# cc2520_cc2592.net
KiCad netlist of a schematic drawn in Altium Designer
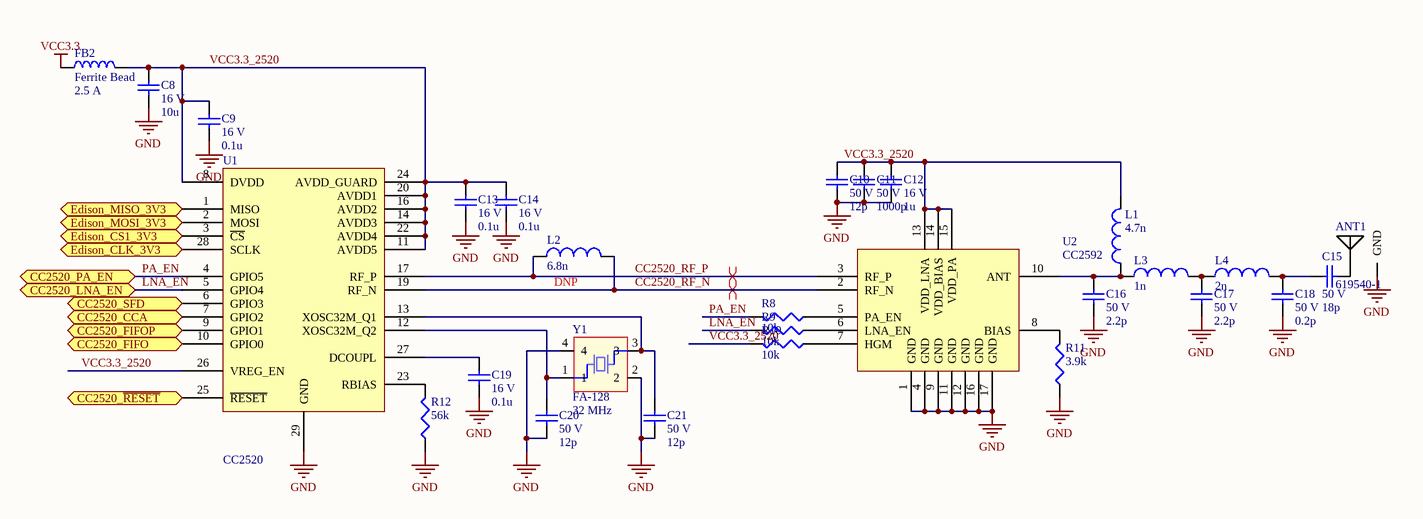
[diagram p0: cc2520_cc2592.SchDoc]

(export (version "E")
  (design (tool "Eeschema 10.0.6"))
  (components
    (comp (ref "ANT1")
      (value "619540-1")
      (footprint "619540-1")
      (description "CONN SMA JACK")
      (libsource (lib "RF") (part "619540-1"))
    )
    (comp (ref "C8")
      (value "10u")
      (footprint "0603")
      (description "10µF ±20% 16V Ceramic Capacitor X6S 0603")
      (fields
        (field (name "TOLERANCE") "20%")
        (field (name "VOLTAGE RATED") "16 V")
        (field (name "MANUFACTURER PART NUMBER") "GRM188C81C106MA73D")
      )
      (libsource (lib "capacitors") (part "GRM188C81C106MA73D"))
    )
    (comp (ref "C9")
      (value "0.1u")
      (footprint "0402")
      (description "0.10µF ±10% 16V Ceramic Capacitor X7R 0402")
      (fields
        (field (name "TOLERANCE") "10%")
        (field (name "VOLTAGE RATED") "16 V")
        (field (name "MANUFACTURER PART NUMBER") "GRM155R71C104KA88D")
      )
      (libsource (lib "capacitors") (part "GRM155R71C104KA88D"))
    )
    (comp (ref "C10")
      (value "12p")
      (footprint "0402")
      (description "12pF ±2% 50V Ceramic Capacitor C0G, NP0 0402")
      (fields
        (field (name "VOLTAGE RATED") "50 V")
        (field (name "TOLERANCE") "2%")
        (field (name "MANUFACTURER PART NUMBER") "500R07S120GV4T")
      )
      (libsource (lib "capacitors") (part "500R07S120GV4T"))
    )
    (comp (ref "C11")
      (value "1000p")
      (footprint "0402")
      (description "1000pF ±5% 50V Ceramic Capacitor C0G, NP0 0402")
      (fields
        (field (name "VOLTAGE RATED") "50 V")
        (field (name "TOLERANCE") "5%")
        (field (name "MANUFACTURER PART NUMBER") "C1005C0G1H102J050BA")
      )
      (libsource (lib "capacitors") (part "C1005C0G1H102J050BA"))
    )
    (comp (ref "C12")
      (value "1u")
      (footprint "0402")
      (description "1µF ±10% 16V Ceramic Capacitor X6S 0402")
      (fields
        (field (name "VOLTAGE RATED") "16 V")
        (field (name "TOLERANCE") "10%")
        (field (name "MANUFACTURER PART NUMBER") "C1005X6S1C105K050BC")
      )
      (libsource (lib "capacitors") (part "C1005X6S1C105K050BC"))
    )
    (comp (ref "C13")
      (value "0.1u")
      (footprint "0402")
      (description "0.10µF ±10% 16V Ceramic Capacitor X7R 0402")
      (fields
        (field (name "TOLERANCE") "10%")
        (field (name "VOLTAGE RATED") "16 V")
        (field (name "MANUFACTURER PART NUMBER") "GRM155R71C104KA88D")
      )
      (libsource (lib "capacitors") (part "GRM155R71C104KA88D"))
    )
    (comp (ref "C14")
      (value "0.1u")
      (footprint "0402")
      (description "0.10µF ±10% 16V Ceramic Capacitor X7R 0402")
      (fields
        (field (name "TOLERANCE") "10%")
        (field (name "VOLTAGE RATED") "16 V")
        (field (name "MANUFACTURER PART NUMBER") "GRM155R71C104KA88D")
      )
      (libsource (lib "capacitors") (part "GRM155R71C104KA88D"))
    )
    (comp (ref "C15")
      (value "18p")
      (footprint "0402")
      (description "18pF ±2% 50V Ceramic Capacitor C0G, NP0 0402")
      (fields
        (field (name "TOLERANCE") "2%")
        (field (name "VOLTAGE RATED") "50 V")
        (field (name "MANUFACTURER PART NUMBER") "500R07S180GV4T")
      )
      (libsource (lib "capacitors") (part "500R07S180GV4T"))
    )
    (comp (ref "C16")
      (value "2.2p")
      (footprint "0402")
      (description "2.2pF ±0.1pF 50V Ceramic Capacitor C0G, NP0")
      (fields
        (field (name "TOLERANCE") "0.1p")
        (field (name "VOLTAGE RATED") "50 V")
        (field (name "MANUFACTURER PART NUMBER") "500R07S2R2BV4T")
      )
      (libsource (lib "capacitors") (part "500R07S2R2BV4T"))
    )
    (comp (ref "C17")
      (value "2.2p")
      (footprint "0402")
      (description "2.2pF ±0.1pF 50V Ceramic Capacitor C0G, NP0")
      (fields
        (field (name "TOLERANCE") "0.1p")
        (field (name "VOLTAGE RATED") "50 V")
        (field (name "MANUFACTURER PART NUMBER") "500R07S2R2BV4T")
      )
      (libsource (lib "capacitors") (part "500R07S2R2BV4T"))
    )
    (comp (ref "C18")
      (value "0.2p")
      (footprint "0402")
      (description "0.20pF ±0.05pF 50V Ceramic Capacitor C0G, NP0 0402")
      (fields
        (field (name "TOLERANCE") "0.05p")
        (field (name "VOLTAGE RATED") "50 V")
        (field (name "MANUFACTURER PART NUMBER") "500R07S0R2AV4T")
      )
      (libsource (lib "capacitors") (part "500R07S0R2AV4T"))
    )
    (comp (ref "C19")
      (value "0.1u")
      (footprint "0402")
      (description "0.10µF ±10% 16V Ceramic Capacitor X7R 0402")
      (fields
        (field (name "TOLERANCE") "10%")
        (field (name "VOLTAGE RATED") "16 V")
        (field (name "MANUFACTURER PART NUMBER") "GRM155R71C104KA88D")
      )
      (libsource (lib "capacitors") (part "GRM155R71C104KA88D"))
    )
    (comp (ref "C20")
      (value "12p")
      (footprint "0402")
      (description "12pF ±2% 50V Ceramic Capacitor C0G, NP0 0402")
      (fields
        (field (name "VOLTAGE RATED") "50 V")
        (field (name "TOLERANCE") "2%")
        (field (name "MANUFACTURER PART NUMBER") "500R07S120GV4T")
      )
      (libsource (lib "capacitors") (part "500R07S120GV4T"))
    )
    (comp (ref "C21")
      (value "12p")
      (footprint "0402")
      (description "12pF ±2% 50V Ceramic Capacitor C0G, NP0 0402")
      (fields
        (field (name "VOLTAGE RATED") "50 V")
        (field (name "TOLERANCE") "2%")
        (field (name "MANUFACTURER PART NUMBER") "500R07S120GV4T")
      )
      (libsource (lib "capacitors") (part "500R07S120GV4T"))
    )
    (comp (ref "FB2")
      (value "Ferrite Bead")
      (footprint "0603")
      (description "FERRITE BEAD 220 OHM 0603")
      (fields
        (field (name "MANUFACTURER PART NUMBER") "BLM18SG221TN1D")
        (field (name "MANUFACTURER") "Murata")
        (field (name "CURRENT RATING (MAX)") "2.5 A")
      )
      (libsource (lib "ferrite_beads") (part "BLM18SG221TN1D"))
    )
    (comp (ref "L1")
      (value "4.7n")
      (footprint "0402")
      (description "4.7nH Unshielded Multilayer Inductor 300mA 180 mOhm Max 0402 (1005 Metric)")
      (fields (field (name "TOLERANCE") "0.3n") (field (name "MANUFACTURER PART NUMBER") "LQG15HS4N7S02D"))
      (libsource (lib "inductors") (part "LQG15HS4N7S02D"))
    )
    (comp (ref "L2")
      (value "6.8n")
      (footprint "0402")
      (description "6.8nH Unshielded Multilayer Inductor 250mA 320 mOhm Max 0402 (1005 Metric)")
      (fields
        (field (name "TOLERANCE") "5%")
        (field (name "MANUFACTURER PART NUMBER") "L-07C6N8JV6T")
        (field (name "NOTE") "DNP")
      )
      (libsource (lib "inductors") (part "L-07C6N8JV6T"))
    )
    (comp (ref "L3")
      (value "1n")
      (footprint "0402")
      (description "1nH Unshielded Multilayer Inductor 300mA 100 mOhm Max 0402 (1005 Metric)")
      (fields (field (name "TOLERANCE") "0.3n") (field (name "MANUFACTURER PART NUMBER") "LQG15HN1N0S02D"))
      (libsource (lib "inductors") (part "LQG15HN1N0S02D"))
    )
    (comp (ref "L4")
      (value "2n")
      (footprint "0402")
      (description "2nH Unshielded Multilayer Inductor 300mA 120 mOhm Max 0402 (1005 Metric)")
      (fields (field (name "TOLERANCE") "0.3n") (field (name "MANUFACTURER PART NUMBER") "LQG15HN2N0S02D"))
      (libsource (lib "inductors") (part "LQG15HN2N0S02D"))
    )
    (comp (ref "R8")
      (value "10k")
      (footprint "0402")
      (description "RES SMD 10K OHM 1% 1/16W 0402")
      (fields (field (name "TOLERANCE") "1%") (field (name "POWER") "1/16 W"))
      (libsource (lib "resistors") (part "CRCW040210K0FKED"))
    )
    (comp (ref "R9")
      (value "10k")
      (footprint "0402")
      (description "RES SMD 10K OHM 1% 1/16W 0402")
      (fields (field (name "TOLERANCE") "1%") (field (name "POWER") "1/16 W"))
      (libsource (lib "resistors") (part "CRCW040210K0FKED"))
    )
    (comp (ref "R10")
      (value "10k")
      (footprint "0402")
      (description "RES SMD 10K OHM 1% 1/16W 0402")
      (fields (field (name "TOLERANCE") "1%") (field (name "POWER") "1/16 W"))
      (libsource (lib "resistors") (part "CRCW040210K0FKED"))
    )
    (comp (ref "R11")
      (value "3.9k")
      (footprint "0402")
      (description "RES SMD 3.9K OHM 1% 1/16W 0402")
      (fields (field (name "TOLERANCE") "1%") (field (name "POWER") "1/16 W"))
      (libsource (lib "resistors") (part "RC0402FR-073K9L"))
    )
    (comp (ref "R12")
      (value "56k")
      (footprint "0402")
      (description "RES SMD 56K OHM 1% 1/16W 0402")
      (fields (field (name "POWER") "1/16 W") (field (name "TOLERANCE") "1%"))
      (libsource (lib "resistors") (part "CRCW040256K0FKED"))
    )
    (comp (ref "U1")
      (value "CC2520")
      (footprint "QFN-28")
      (description "2.4 GHZ IEEE 802.15.4/ZIGBEE® RF TRANSCEIVER")
      (libsource (lib "RF") (part "CC2520"))
    )
    (comp (ref "U2")
      (value "CC2592")
      (footprint "RF:QFN-16")
      (description "2.4-GHz Range Extender")
      (libsource (lib "RF") (part "CC2592"))
    )
    (comp (ref "Y1")
      (value "FA-128")
      (footprint "FA-128")
      (description "MHz Range Crystal Unit")
      (fields (field (name "FREQUENCY") "32 MHz"))
      (libsource (lib "crystal oscillators") (part "FA-128"))
    )
  )
  (nets
    (net (code "1") (name "/CC2520_CCA") (class "Default")
      (node (ref "U1") (pin "7") (pinfunction "GPIO2_7") (pintype "passive"))
    )
    (net (code "2") (name "/CC2520_FIFO") (class "Default")
      (node (ref "U1") (pin "10") (pinfunction "GPIO0_10") (pintype "passive"))
    )
    (net (code "3") (name "/CC2520_FIFOP") (class "Default")
      (node (ref "U1") (pin "9") (pinfunction "GPIO1_9") (pintype "passive"))
    )
    (net (code "4") (name "/CC2520_RF_N") (class "Default")
      (node (ref "L2") (pin "1") (pintype "passive"))
      (node (ref "U1") (pin "19") (pinfunction "RF_N_19") (pintype "passive"))
      (node (ref "U2") (pin "2") (pinfunction "RF_N_2") (pintype "passive"))
    )
    (net (code "5") (name "/CC2520_RF_P") (class "Default")
      (node (ref "L2") (pin "2") (pintype "passive"))
      (node (ref "U1") (pin "17") (pinfunction "RF_P_17") (pintype "passive"))
      (node (ref "U2") (pin "3") (pinfunction "RF_P_3") (pintype "passive"))
    )
    (net (code "6") (name "/CC2520_SFD") (class "Default")
      (node (ref "U1") (pin "6") (pinfunction "GPIO3_6") (pintype "passive"))
    )
    (net (code "7") (name "/CC2520_~{RESET}") (class "Default")
      (node (ref "U1") (pin "25") (pinfunction "~{RESET}_25") (pintype "passive"))
    )
    (net (code "8") (name "/Edison_CLK_3V3") (class "Default")
      (node (ref "U1") (pin "28") (pinfunction "SCLK_28") (pintype "passive"))
    )
    (net (code "9") (name "/Edison_CS1_3V3") (class "Default")
      (node (ref "U1") (pin "3") (pinfunction "~{CS}_3") (pintype "passive"))
    )
    (net (code "10") (name "/Edison_MISO_3V3") (class "Default")
      (node (ref "U1") (pin "1") (pinfunction "MISO_1") (pintype "passive"))
    )
    (net (code "11") (name "/Edison_MOSI_3V3") (class "Default")
      (node (ref "U1") (pin "2") (pinfunction "MOSI_2") (pintype "passive"))
    )
    (net (code "12") (name "/LNA_EN") (class "Default")
      (node (ref "R9") (pin "1") (pintype "passive"))
      (node (ref "U1") (pin "5") (pinfunction "GPIO4_5") (pintype "passive"))
    )
    (net (code "13") (name "/PA_EN") (class "Default")
      (node (ref "R8") (pin "1") (pintype "passive"))
      (node (ref "U1") (pin "4") (pinfunction "GPIO5_4") (pintype "passive"))
    )
    (net (code "14") (name "/VCC3.3_2520") (class "Default")
      (node (ref "C10") (pin "1") (pintype "passive"))
      (node (ref "C11") (pin "1") (pintype "passive"))
      (node (ref "C12") (pin "1") (pintype "passive"))
      (node (ref "C13") (pin "1") (pintype "passive"))
      (node (ref "C14") (pin "1") (pintype "passive"))
      (node (ref "C8") (pin "1") (pintype "passive"))
      (node (ref "C9") (pin "1") (pintype "passive"))
      (node (ref "FB2") (pin "1") (pintype "passive"))
      (node (ref "L1") (pin "1") (pintype "passive"))
      (node (ref "R10") (pin "1") (pintype "passive"))
      (node (ref "U1") (pin "11") (pinfunction "AVDD5_11") (pintype "passive"))
      (node (ref "U1") (pin "14") (pinfunction "AVDD3_14") (pintype "passive"))
      (node (ref "U1") (pin "16") (pinfunction "AVDD2_16") (pintype "passive"))
      (node (ref "U1") (pin "20") (pinfunction "AVDD1_20") (pintype "passive"))
      (node (ref "U1") (pin "22") (pinfunction "AVDD4_22") (pintype "passive"))
      (node (ref "U1") (pin "24") (pinfunction "AVDD_GUARD_24") (pintype "passive"))
      (node (ref "U1") (pin "26") (pinfunction "VREG_EN_26") (pintype "passive"))
      (node (ref "U1") (pin "8") (pinfunction "DVDD_8") (pintype "passive"))
      (node (ref "U2") (pin "13") (pinfunction "VDD_LNA_13") (pintype "passive"))
      (node (ref "U2") (pin "14") (pinfunction "VDD_BIAS_14") (pintype "passive"))
      (node (ref "U2") (pin "15") (pinfunction "VDD_PA_15") (pintype "passive"))
    )
    (net (code "15") (name "GND") (class "Default")
      (node (ref "ANT1") (pin "1") (pinfunction "GND_1") (pintype "power_in"))
      (node (ref "C10") (pin "2") (pintype "passive"))
      (node (ref "C11") (pin "2") (pintype "passive"))
      (node (ref "C12") (pin "2") (pintype "passive"))
      (node (ref "C13") (pin "2") (pintype "passive"))
      (node (ref "C14") (pin "2") (pintype "passive"))
      (node (ref "C16") (pin "2") (pintype "passive"))
      (node (ref "C17") (pin "2") (pintype "passive"))
      (node (ref "C18") (pin "2") (pintype "passive"))
      (node (ref "C19") (pin "2") (pintype "passive"))
      (node (ref "C20") (pin "1") (pintype "passive"))
      (node (ref "C21") (pin "1") (pintype "passive"))
      (node (ref "C8") (pin "2") (pintype "passive"))
      (node (ref "C9") (pin "2") (pintype "passive"))
      (node (ref "R11") (pin "2") (pintype "passive"))
      (node (ref "R12") (pin "2") (pintype "passive"))
      (node (ref "U1") (pin "29") (pinfunction "GND_29") (pintype "passive"))
      (node (ref "U2") (pin "1") (pinfunction "GND_1") (pintype "passive"))
      (node (ref "U2") (pin "11") (pinfunction "GND_11") (pintype "passive"))
      (node (ref "U2") (pin "12") (pinfunction "GND_12") (pintype "passive"))
      (node (ref "U2") (pin "16") (pinfunction "GND_16") (pintype "passive"))
      (node (ref "U2") (pin "17") (pinfunction "GND_17") (pintype "passive"))
      (node (ref "U2") (pin "4") (pinfunction "GND_4") (pintype "passive"))
      (node (ref "U2") (pin "9") (pinfunction "GND_9") (pintype "passive"))
      (node (ref "Y1") (pin "2") (pinfunction "2_2") (pintype "passive"))
      (node (ref "Y1") (pin "4") (pinfunction "4_4") (pintype "passive"))
    )
    (net (code "16") (name "Net-(ANT1-Pad2)") (class "Default")
      (node (ref "ANT1") (pin "2") (pintype "passive"))
      (node (ref "C15") (pin "2") (pintype "passive"))
    )
    (net (code "17") (name "Net-(C15-Pad1)") (class "Default")
      (node (ref "C15") (pin "1") (pintype "passive"))
      (node (ref "C18") (pin "1") (pintype "passive"))
      (node (ref "L4") (pin "1") (pintype "passive"))
    )
    (net (code "18") (name "Net-(C17-Pad1)") (class "Default")
      (node (ref "C17") (pin "1") (pintype "passive"))
      (node (ref "L3") (pin "1") (pintype "passive"))
      (node (ref "L4") (pin "2") (pintype "passive"))
    )
    (net (code "19") (name "Net-(U1-DCOUPL)") (class "Default")
      (node (ref "C19") (pin "1") (pintype "passive"))
      (node (ref "U1") (pin "27") (pinfunction "DCOUPL_27") (pintype "passive"))
    )
    (net (code "20") (name "Net-(U1-RBIAS)") (class "Default")
      (node (ref "R12") (pin "1") (pintype "passive"))
      (node (ref "U1") (pin "23") (pinfunction "RBIAS_23") (pintype "passive"))
    )
    (net (code "21") (name "Net-(U1-XOSC32M_Q1)") (class "Default")
      (node (ref "C21") (pin "2") (pintype "passive"))
      (node (ref "U1") (pin "13") (pinfunction "XOSC32M_Q1_13") (pintype "passive"))
      (node (ref "Y1") (pin "3") (pinfunction "3_3") (pintype "passive"))
    )
    (net (code "22") (name "Net-(U1-XOSC32M_Q2)") (class "Default")
      (node (ref "C20") (pin "2") (pintype "passive"))
      (node (ref "U1") (pin "12") (pinfunction "XOSC32M_Q2_12") (pintype "passive"))
      (node (ref "Y1") (pin "1") (pinfunction "1_1") (pintype "passive"))
    )
    (net (code "23") (name "Net-(U2-ANT)") (class "Default")
      (node (ref "C16") (pin "1") (pintype "passive"))
      (node (ref "L1") (pin "2") (pintype "passive"))
      (node (ref "L3") (pin "2") (pintype "passive"))
      (node (ref "U2") (pin "10") (pinfunction "ANT_10") (pintype "passive"))
    )
    (net (code "24") (name "Net-(U2-BIAS)") (class "Default")
      (node (ref "R11") (pin "1") (pintype "passive"))
      (node (ref "U2") (pin "8") (pinfunction "BIAS_8") (pintype "passive"))
    )
    (net (code "25") (name "Net-(U2-HGM)") (class "Default")
      (node (ref "R10") (pin "2") (pintype "passive"))
      (node (ref "U2") (pin "7") (pinfunction "HGM_7") (pintype "passive"))
    )
    (net (code "26") (name "Net-(U2-LNA_EN)") (class "Default")
      (node (ref "R9") (pin "2") (pintype "passive"))
      (node (ref "U2") (pin "6") (pinfunction "LNA_EN_6") (pintype "passive"))
    )
    (net (code "27") (name "Net-(U2-PA_EN)") (class "Default")
      (node (ref "R8") (pin "2") (pintype "passive"))
      (node (ref "U2") (pin "5") (pinfunction "PA_EN_5") (pintype "passive"))
    )
    (net (code "28") (name "VCC3.3") (class "Default") (node (ref "FB2") (pin "2") (pintype "passive")))
  )
)
